# PROC010B_PMIC_Reference.net
KiCad netlist of a schematic drawn in Altium Designer
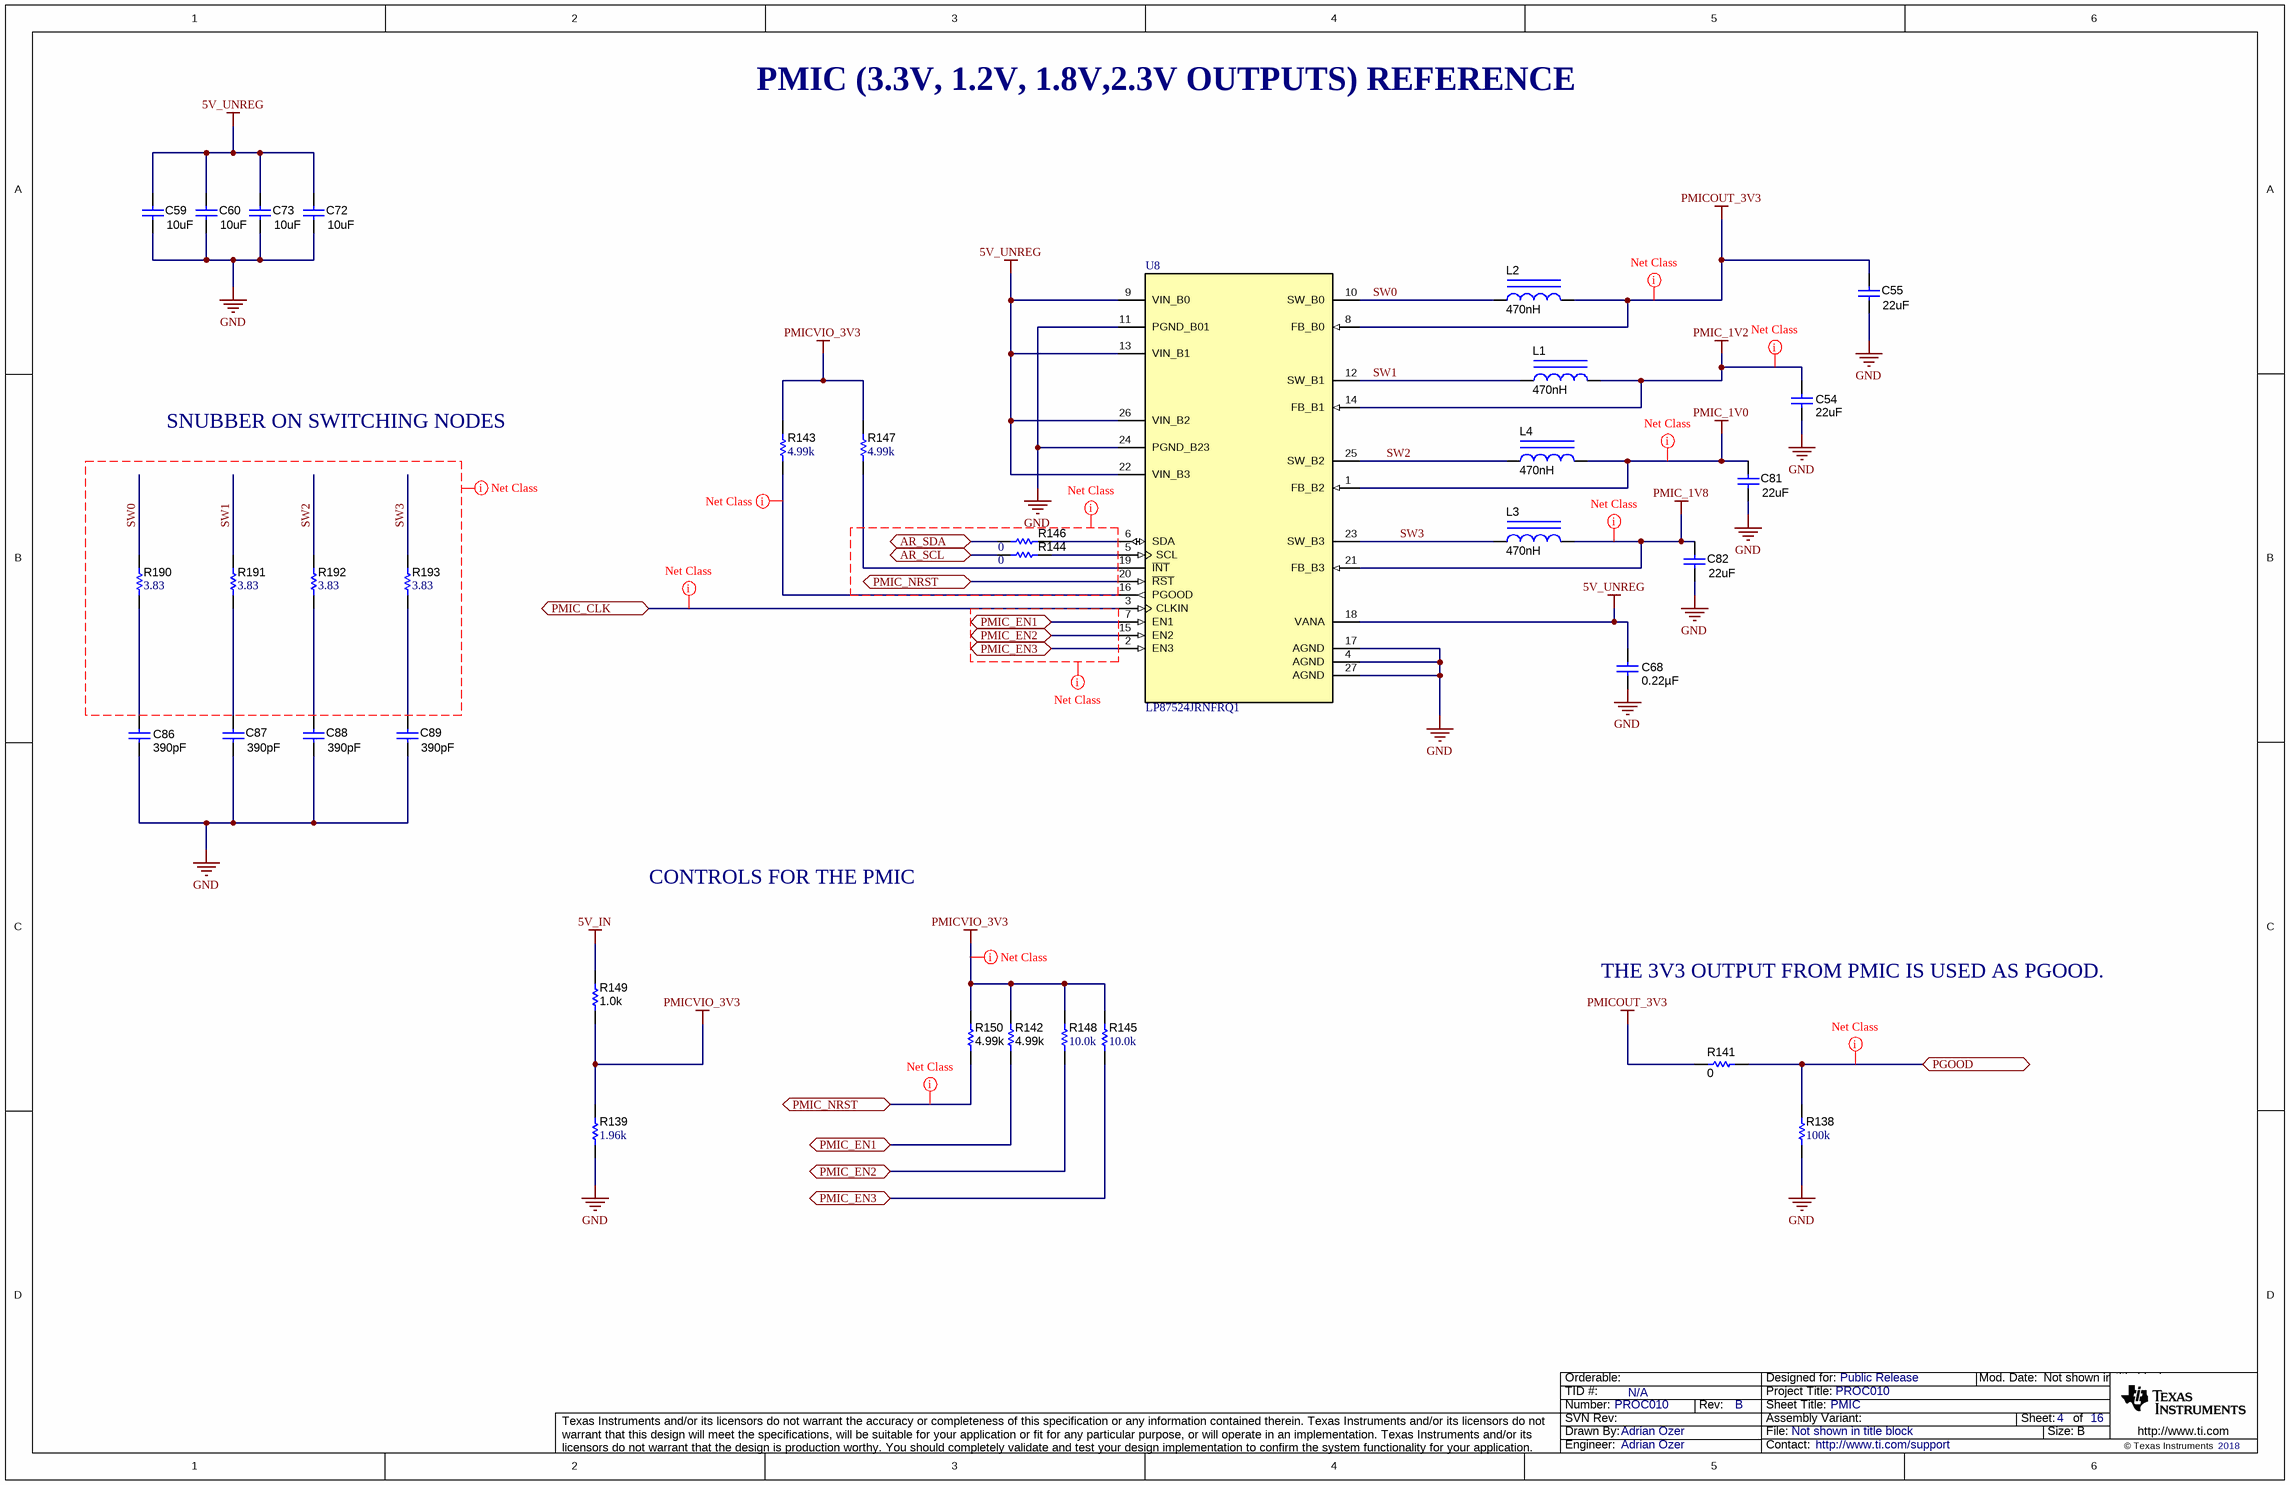
[diagram p0: PROC010B_PMIC_Reference.SchDoc]

(export (version "E")
  (design (tool "Eeschema 10.0.6"))
  (components
    (comp (ref "C54")
      (value "GCM31CR71A226KE02")
      (footprint "1206_180")
      (description "CAP, CERM, 22 uF, 10 V, +/- 10%, X7R, AEC-Q200 Grade 1, 1206")
      (fields
        (field (name "MANUFACTURER") "MuRata")
        (field (name "VALUEDISPLAYED") "22uF")
        (field (name "PUBLISHER") "Texas Instruments")
      )
      (libsource (lib "Altium Vault - TI") (part "CMP-0008811-2"))
    )
    (comp (ref "C55")
      (value "GCM31CR71A226KE02")
      (footprint "1206_180")
      (description "CAP, CERM, 22 uF, 10 V, +/- 10%, X7R, AEC-Q200 Grade 1, 1206")
      (fields
        (field (name "MANUFACTURER") "MuRata")
        (field (name "VALUEDISPLAYED") "22uF")
        (field (name "PUBLISHER") "Texas Instruments")
      )
      (libsource (lib "Altium Vault - TI") (part "Capacitor"))
    )
    (comp (ref "C59")
      (value "GCM21BR71A106KE22L")
      (footprint "0805_HV1")
      (description "CAP, CERM, 10 uF, 10 V, +/- 10%, X7R, 0805")
      (fields
        (field (name "MANUFACTURER") "MuRata")
        (field (name "VALUEDISPLAYED") "10uF")
        (field (name "PUBLISHER") "Texas Instruments")
      )
      (libsource (lib "Altium Vault - TI") (part "CMP-0008017-2"))
    )
    (comp (ref "C60")
      (value "GCM21BR71A106KE22L")
      (footprint "0805_HV1")
      (description "CAP, CERM, 10 uF, 10 V, +/- 10%, X7R, 0805")
      (fields
        (field (name "MANUFACTURER") "MuRata")
        (field (name "VALUEDISPLAYED") "10uF")
        (field (name "PUBLISHER") "Texas Instruments")
      )
      (libsource (lib "Altium Vault - TI") (part "CMP-0008017-2"))
    )
    (comp (ref "C68")
      (value "GCM155R71C224KE02D")
      (footprint "0402L")
      (description "CAP, CERM, 0.22 µF, 16 V,+/- 10%, X7R, AEC-Q200 Grade 1, 0402")
      (fields (field (name "MANUFACTURER") "MuRata") (field (name "VALUEDISPLAYED") "0.22µF"))
      (libsource (lib "Altium Vault - TI") (part "CMP-0078265-1"))
    )
    (comp (ref "C72")
      (value "GCM21BR71A106KE22L")
      (footprint "0805_HV1")
      (description "CAP, CERM, 10 uF, 10 V, +/- 10%, X7R, 0805")
      (fields
        (field (name "MANUFACTURER") "MuRata")
        (field (name "VALUEDISPLAYED") "10uF")
        (field (name "PUBLISHER") "Texas Instruments")
      )
      (libsource (lib "Altium Vault - TI") (part "CMP-0008017-2"))
    )
    (comp (ref "C73")
      (value "GCM21BR71A106KE22L")
      (footprint "0805_HV1")
      (description "CAP, CERM, 10 uF, 10 V, +/- 10%, X7R, 0805")
      (fields
        (field (name "MANUFACTURER") "MuRata")
        (field (name "VALUEDISPLAYED") "10uF")
        (field (name "PUBLISHER") "Texas Instruments")
      )
      (libsource (lib "Altium Vault - TI") (part "CMP-0008017-2"))
    )
    (comp (ref "C81")
      (value "GCM31CR71A226KE02")
      (footprint "1206_180")
      (description "CAP, CERM, 22 uF, 10 V, +/- 10%, X7R, AEC-Q200 Grade 1, 1206")
      (fields
        (field (name "MANUFACTURER") "MuRata")
        (field (name "VALUEDISPLAYED") "22uF")
        (field (name "PUBLISHER") "Texas Instruments")
      )
      (libsource (lib "Altium Vault - TI") (part "Capacitor"))
    )
    (comp (ref "C82")
      (value "GCM31CR71A226KE02")
      (footprint "1206_180")
      (description "CAP, CERM, 22 uF, 10 V, +/- 10%, X7R, AEC-Q200 Grade 1, 1206")
      (fields
        (field (name "MANUFACTURER") "MuRata")
        (field (name "VALUEDISPLAYED") "22uF")
        (field (name "PUBLISHER") "Texas Instruments")
      )
      (libsource (lib "Altium Vault - TI") (part "Capacitor"))
    )
    (comp (ref "C86")
      (value "CGA2B2NP01H391J050BA")
      (footprint "0402L")
      (description "CAP, CERM, 390 pF, 50 V,+/- 5%, C0G/NP0, AEC-Q200 Grade 0, 0402")
      (fields (field (name "MANUFACTURER") "TDK") (field (name "VALUEDISPLAYED") "390pF"))
      (libsource (lib "Altium Vault - TI") (part "Capacitor"))
    )
    (comp (ref "C87")
      (value "CGA2B2NP01H391J050BA")
      (footprint "0402L")
      (description "CAP, CERM, 390 pF, 50 V,+/- 5%, C0G/NP0, AEC-Q200 Grade 0, 0402")
      (fields (field (name "MANUFACTURER") "TDK") (field (name "VALUEDISPLAYED") "390pF"))
      (libsource (lib "Altium Vault - TI") (part "Capacitor"))
    )
    (comp (ref "C88")
      (value "CGA2B2NP01H391J050BA")
      (footprint "0402L")
      (description "CAP, CERM, 390 pF, 50 V,+/- 5%, C0G/NP0, AEC-Q200 Grade 0, 0402")
      (fields (field (name "MANUFACTURER") "TDK") (field (name "VALUEDISPLAYED") "390pF"))
      (libsource (lib "Altium Vault - TI") (part "Capacitor"))
    )
    (comp (ref "C89")
      (value "CGA2B2NP01H391J050BA")
      (footprint "0402L")
      (description "CAP, CERM, 390 pF, 50 V,+/- 5%, C0G/NP0, AEC-Q200 Grade 0, 0402")
      (fields (field (name "MANUFACTURER") "TDK") (field (name "VALUEDISPLAYED") "390pF"))
      (libsource (lib "Altium Vault - TI") (part "Capacitor"))
    )
    (comp (ref "L1")
      (value "DFE252012P-R47M=P2")
      (footprint "DFE252012P")
      (description "Inductor, Shielded, 470 nH, 4.7 A, 0.021 ohm, SMD")
      (fields
        (field (name "MANUFACTURER") "MuRata Toko")
        (field (name "VALUEDISPLAYED") "470nH")
        (field (name "PUBLISHER") "Texas Instruments")
      )
      (libsource (lib "Altium Vault - TI") (part "Inductor_Iron"))
    )
    (comp (ref "L2")
      (value "DFE252012P-R47M=P2")
      (footprint "DFE252012P")
      (description "Inductor, Shielded, 470 nH, 4.7 A, 0.021 ohm, SMD")
      (fields
        (field (name "MANUFACTURER") "MuRata Toko")
        (field (name "VALUEDISPLAYED") "470nH")
        (field (name "PUBLISHER") "Texas Instruments")
      )
      (libsource (lib "Altium Vault - TI") (part "Inductor_Iron"))
    )
    (comp (ref "L3")
      (value "DFE252012P-R47M=P2")
      (footprint "DFE252012P")
      (description "Inductor, Shielded, 470 nH, 4.7 A, 0.021 ohm, SMD")
      (fields
        (field (name "MANUFACTURER") "MuRata Toko")
        (field (name "VALUEDISPLAYED") "470nH")
        (field (name "PUBLISHER") "Texas Instruments")
      )
      (libsource (lib "Altium Vault - TI") (part "Inductor_Iron"))
    )
    (comp (ref "L4")
      (value "DFE252012P-R47M=P2")
      (footprint "DFE252012P")
      (description "Inductor, Shielded, 470 nH, 4.7 A, 0.021 ohm, SMD")
      (fields
        (field (name "MANUFACTURER") "MuRata Toko")
        (field (name "VALUEDISPLAYED") "470nH")
        (field (name "PUBLISHER") "Texas Instruments")
      )
      (libsource (lib "Altium Vault - TI") (part "Inductor_Iron"))
    )
    (comp (ref "R138")
      (value "CRCW0402100KFKED")
      (footprint "0402L")
      (description "RES, 100 k, 1%, 0.063 W, AEC-Q200 Grade 0, 0402")
      (fields (field (name "MANUFACTURER") "Vishay-Dale") (field (name "VALUEDISPLAYED") "100k"))
      (libsource (lib "Altium Vault - TI") (part "Resistor"))
    )
    (comp (ref "R139")
      (value "CRCW04021K96FKED")
      (footprint "0402L")
      (description "RES, 1.96 k, 1%, 0.063 W, AEC-Q200 Grade 0, 0402")
      (fields (field (name "MANUFACTURER") "Vishay-Dale") (field (name "VALUEDISPLAYED") "1.96k"))
      (libsource (lib "Altium Vault - TI") (part "Resistor"))
    )
    (comp (ref "R141")
      (value "ERJ-2GE0R00X")
      (footprint "0402L")
      (description "RES, 0, 5%, 0.063 W, 0402")
      (fields
        (field (name "MANUFACTURER") "Panasonic")
        (field (name "VALUEDISPLAYED") "0")
        (field (name "PUBLISHER") "Texas Instruments")
      )
      (libsource (lib "Altium Vault - TI") (part "Resistor"))
    )
    (comp (ref "R142")
      (value "ERJ-2RKF4991X")
      (footprint "0402L")
      (description "RES, 4.99 k, 1%, 0.1 W, AEC-Q200 Grade 0, 0402")
      (fields
        (field (name "MANUFACTURER") "Panasonic")
        (field (name "VALUEDISPLAYED") "4.99k")
        (field (name "PUBLISHER") "Texas Instruments")
      )
      (libsource (lib "Altium Vault - TI") (part "Resistor"))
    )
    (comp (ref "R143")
      (value "CRCW04024K99FKED")
      (footprint "0402L")
      (description "RES, 4.99 k, 1%, 0.063 W, AEC-Q200 Grade 0, 0402")
      (fields (field (name "MANUFACTURER") "Vishay-Dale") (field (name "VALUEDISPLAYED") "4.99k"))
      (libsource (lib "Altium Vault - TI") (part "Resistor"))
    )
    (comp (ref "R144")
      (value "CRCW02010000Z0ED")
      (footprint "0201_Silk")
      (description "RES, 0, 5%, 0.05 W, 0201")
      (fields (field (name "MANUFACTURER") "Vishay-Dale") (field (name "VALUEDISPLAYED") "0"))
      (libsource (lib "Altium Vault - TI") (part "Resistor"))
    )
    (comp (ref "R145")
      (value "CRCW040210K0FKED")
      (footprint "0402L")
      (description "RES, 10.0 k, 1%, 0.063 W, AEC-Q200 Grade 0, 0402")
      (fields (field (name "MANUFACTURER") "Vishay-Dale") (field (name "VALUEDISPLAYED") "10.0k"))
      (libsource (lib "Altium Vault - TI") (part "CMP-0025958-3"))
    )
    (comp (ref "R146")
      (value "CRCW02010000Z0ED")
      (footprint "0201_Silk")
      (description "RES, 0, 5%, 0.05 W, 0201")
      (fields (field (name "MANUFACTURER") "Vishay-Dale") (field (name "VALUEDISPLAYED") "0"))
      (libsource (lib "Altium Vault - TI") (part "Resistor"))
    )
    (comp (ref "R147")
      (value "CRCW04024K99FKED")
      (footprint "0402L")
      (description "RES, 4.99 k, 1%, 0.063 W, AEC-Q200 Grade 0, 0402")
      (fields (field (name "MANUFACTURER") "Vishay-Dale") (field (name "VALUEDISPLAYED") "4.99k"))
      (libsource (lib "Altium Vault - TI") (part "Resistor"))
    )
    (comp (ref "R148")
      (value "CRCW040210K0FKED")
      (footprint "0402L")
      (description "RES, 10.0 k, 1%, 0.063 W, AEC-Q200 Grade 0, 0402")
      (fields (field (name "MANUFACTURER") "Vishay-Dale") (field (name "VALUEDISPLAYED") "10.0k"))
      (libsource (lib "Altium Vault - TI") (part "Resistor"))
    )
    (comp (ref "R149")
      (value "ERJ-2GEJ102X")
      (footprint "0402L")
      (description "RES, 1.0 k, 5%, 0.1 W, AEC-Q200 Grade 0, 0402")
      (fields (field (name "MANUFACTURER") "Panasonic") (field (name "VALUEDISPLAYED") "1.0k"))
      (libsource (lib "Altium Vault - TI") (part "Resistor"))
    )
    (comp (ref "R150")
      (value "ERJ-2RKF4991X")
      (footprint "0402L")
      (description "RES, 4.99 k, 1%, 0.1 W, AEC-Q200 Grade 0, 0402")
      (fields
        (field (name "MANUFACTURER") "Panasonic")
        (field (name "VALUEDISPLAYED") "4.99k")
        (field (name "PUBLISHER") "Texas Instruments")
      )
      (libsource (lib "Altium Vault - TI") (part "Resistor"))
    )
    (comp (ref "R190")
      (value "CRCW04023R83FKED")
      (footprint "0402L")
      (description "RES, 3.83, 1%, 0.063 W, AEC-Q200 Grade 0, 0402")
      (fields (field (name "MANUFACTURER") "Vishay-Dale") (field (name "VALUEDISPLAYED") "3.83"))
      (libsource (lib "Altium Vault - TI") (part "Resistor"))
    )
    (comp (ref "R191")
      (value "CRCW04023R83FKED")
      (footprint "0402L")
      (description "RES, 3.83, 1%, 0.063 W, AEC-Q200 Grade 0, 0402")
      (fields (field (name "MANUFACTURER") "Vishay-Dale") (field (name "VALUEDISPLAYED") "3.83"))
      (libsource (lib "Altium Vault - TI") (part "Resistor"))
    )
    (comp (ref "R192")
      (value "CRCW04023R83FKED")
      (footprint "0402L")
      (description "RES, 3.83, 1%, 0.063 W, AEC-Q200 Grade 0, 0402")
      (fields (field (name "MANUFACTURER") "Vishay-Dale") (field (name "VALUEDISPLAYED") "3.83"))
      (libsource (lib "Altium Vault - TI") (part "Resistor"))
    )
    (comp (ref "R193")
      (value "CRCW04023R83FKED")
      (footprint "0402L")
      (description "RES, 3.83, 1%, 0.063 W, AEC-Q200 Grade 0, 0402")
      (fields (field (name "MANUFACTURER") "Vishay-Dale") (field (name "VALUEDISPLAYED") "3.83"))
      (libsource (lib "Altium Vault - TI") (part "Resistor"))
    )
    (comp (ref "U8")
      (value "LP87524JRNFRQ1")
      (footprint "RNF0026C")
      (description "4-A + 2.5-A + Two 1.5-A Buck Converters With Integrated Switches, RNF0026C (VQFN-HR-26)")
      (fields
        (field (name "ALTERNATE PARTNUMBER") "LP87524JRNFTQ1")
        (field (name "MANUFACTURER") "Texas Instruments")
        (field (name "PARTNUMBER") "LP87524JRNFRQ1")
      )
      (libsource (lib "Altium Vault - TI") (part "CMP-0079120-1"))
    )
  )
  (nets
    (net (code "1") (name "/AR_SCL") (class "Default")
      (node (ref "R144") (pin "1") (pinfunction "1_1") (pintype "passive"))
    )
    (net (code "2") (name "/AR_SDA") (class "Default")
      (node (ref "R146") (pin "2") (pinfunction "2_2") (pintype "passive"))
    )
    (net (code "3") (name "/PGOOD") (class "Default")
      (node (ref "R138") (pin "2") (pinfunction "2_2") (pintype "passive"))
      (node (ref "R141") (pin "2") (pinfunction "2_2") (pintype "passive"))
    )
    (net (code "4") (name "/PMIC_CLK") (class "Default")
      (node (ref "U8") (pin "3") (pinfunction "CLKIN_3") (pintype "input"))
    )
    (net (code "5") (name "/PMIC_EN1") (class "Default")
      (node (ref "R142") (pin "1") (pinfunction "1_1") (pintype "passive"))
      (node (ref "U8") (pin "7") (pinfunction "EN1_7") (pintype "input"))
    )
    (net (code "6") (name "/PMIC_EN2") (class "Default")
      (node (ref "R148") (pin "1") (pinfunction "1_1") (pintype "passive"))
      (node (ref "U8") (pin "15") (pinfunction "EN2_15") (pintype "input"))
    )
    (net (code "7") (name "/PMIC_EN3") (class "Default")
      (node (ref "R145") (pin "1") (pinfunction "1_1") (pintype "passive"))
      (node (ref "U8") (pin "2") (pinfunction "EN3_2") (pintype "input"))
    )
    (net (code "8") (name "/PMIC_NRST") (class "Default")
      (node (ref "R150") (pin "2") (pinfunction "2_2") (pintype "passive"))
      (node (ref "U8") (pin "20") (pinfunction "RST_20") (pintype "input"))
    )
    (net (code "9") (name "/SW0") (class "Default")
      (node (ref "L2") (pin "1") (pinfunction "1_1") (pintype "passive"))
      (node (ref "R190") (pin "2") (pinfunction "2_2") (pintype "passive"))
      (node (ref "U8") (pin "10") (pinfunction "SW_B0_10") (pintype "power_in"))
    )
    (net (code "10") (name "/SW1") (class "Default")
      (node (ref "L1") (pin "1") (pinfunction "1_1") (pintype "passive"))
      (node (ref "R191") (pin "2") (pinfunction "2_2") (pintype "passive"))
      (node (ref "U8") (pin "12") (pinfunction "SW_B1_12") (pintype "power_in"))
    )
    (net (code "11") (name "/SW2") (class "Default")
      (node (ref "L4") (pin "1") (pinfunction "1_1") (pintype "passive"))
      (node (ref "R192") (pin "2") (pinfunction "2_2") (pintype "passive"))
      (node (ref "U8") (pin "25") (pinfunction "SW_B2_25") (pintype "power_in"))
    )
    (net (code "12") (name "/SW3") (class "Default")
      (node (ref "L3") (pin "1") (pinfunction "1_1") (pintype "passive"))
      (node (ref "R193") (pin "2") (pinfunction "2_2") (pintype "passive"))
      (node (ref "U8") (pin "23") (pinfunction "SW_B3_23") (pintype "power_in"))
    )
    (net (code "13") (name "5V_IN") (class "Default")
      (node (ref "R149") (pin "2") (pinfunction "2_2") (pintype "passive"))
    )
    (net (code "14") (name "5V_UNREG") (class "Default")
      (node (ref "C59") (pin "2") (pinfunction "2_2") (pintype "passive"))
      (node (ref "C60") (pin "2") (pinfunction "2_2") (pintype "passive"))
      (node (ref "C68") (pin "2") (pinfunction "2_2") (pintype "passive"))
      (node (ref "C72") (pin "2") (pinfunction "2_2") (pintype "passive"))
      (node (ref "C73") (pin "2") (pinfunction "2_2") (pintype "passive"))
      (node (ref "U8") (pin "13") (pinfunction "VIN_B1_13") (pintype "power_in"))
      (node (ref "U8") (pin "18") (pinfunction "VANA_18") (pintype "power_in"))
      (node (ref "U8") (pin "22") (pinfunction "VIN_B3_22") (pintype "power_in"))
      (node (ref "U8") (pin "26") (pinfunction "VIN_B2_26") (pintype "power_in"))
      (node (ref "U8") (pin "9") (pinfunction "VIN_B0_9") (pintype "power_in"))
    )
    (net (code "15") (name "GND") (class "Default")
      (node (ref "C54") (pin "1") (pinfunction "1_1") (pintype "passive"))
      (node (ref "C55") (pin "1") (pinfunction "1_1") (pintype "passive"))
      (node (ref "C59") (pin "1") (pinfunction "1_1") (pintype "passive"))
      (node (ref "C60") (pin "1") (pinfunction "1_1") (pintype "passive"))
      (node (ref "C68") (pin "1") (pinfunction "1_1") (pintype "passive"))
      (node (ref "C72") (pin "1") (pinfunction "1_1") (pintype "passive"))
      (node (ref "C73") (pin "1") (pinfunction "1_1") (pintype "passive"))
      (node (ref "C81") (pin "1") (pinfunction "1_1") (pintype "passive"))
      (node (ref "C82") (pin "1") (pinfunction "1_1") (pintype "passive"))
      (node (ref "C86") (pin "1") (pinfunction "1_1") (pintype "passive"))
      (node (ref "C87") (pin "1") (pinfunction "1_1") (pintype "passive"))
      (node (ref "C88") (pin "1") (pinfunction "1_1") (pintype "passive"))
      (node (ref "C89") (pin "1") (pinfunction "1_1") (pintype "passive"))
      (node (ref "R138") (pin "1") (pinfunction "1_1") (pintype "passive"))
      (node (ref "R139") (pin "1") (pinfunction "1_1") (pintype "passive"))
      (node (ref "U8") (pin "11") (pinfunction "PGND_B01_11") (pintype "power_in"))
      (node (ref "U8") (pin "17") (pinfunction "AGND_17") (pintype "power_in"))
      (node (ref "U8") (pin "24") (pinfunction "PGND_B23_24") (pintype "power_in"))
      (node (ref "U8") (pin "27") (pinfunction "AGND_27") (pintype "power_in"))
      (node (ref "U8") (pin "4") (pinfunction "AGND_4") (pintype "power_in"))
    )
    (net (code "16") (name "Net-(C86-Pad2)") (class "Default")
      (node (ref "C86") (pin "2") (pinfunction "2_2") (pintype "passive"))
      (node (ref "R190") (pin "1") (pinfunction "1_1") (pintype "passive"))
    )
    (net (code "17") (name "Net-(C87-Pad2)") (class "Default")
      (node (ref "C87") (pin "2") (pinfunction "2_2") (pintype "passive"))
      (node (ref "R191") (pin "1") (pinfunction "1_1") (pintype "passive"))
    )
    (net (code "18") (name "Net-(C88-Pad2)") (class "Default")
      (node (ref "C88") (pin "2") (pinfunction "2_2") (pintype "passive"))
      (node (ref "R192") (pin "1") (pinfunction "1_1") (pintype "passive"))
    )
    (net (code "19") (name "Net-(C89-Pad2)") (class "Default")
      (node (ref "C89") (pin "2") (pinfunction "2_2") (pintype "passive"))
      (node (ref "R193") (pin "1") (pinfunction "1_1") (pintype "passive"))
    )
    (net (code "20") (name "Net-(U8-INT)") (class "Default")
      (node (ref "R147") (pin "1") (pinfunction "1_1") (pintype "passive"))
      (node (ref "U8") (pin "19") (pinfunction "INT_19") (pintype "open_collector"))
    )
    (net (code "21") (name "Net-(U8-PGOOD)") (class "Default")
      (node (ref "R143") (pin "1") (pinfunction "1_1") (pintype "passive"))
      (node (ref "U8") (pin "16") (pinfunction "PGOOD_16") (pintype "output"))
    )
    (net (code "22") (name "Net-(U8-SCL)") (class "Default")
      (node (ref "R144") (pin "2") (pinfunction "2_2") (pintype "passive"))
      (node (ref "U8") (pin "5") (pinfunction "SCL_5") (pintype "input"))
    )
    (net (code "23") (name "Net-(U8-SDA)") (class "Default")
      (node (ref "R146") (pin "1") (pinfunction "1_1") (pintype "passive"))
      (node (ref "U8") (pin "6") (pinfunction "SDA_6") (pintype "bidirectional"))
    )
    (net (code "24") (name "PMICOUT_3V3") (class "Default")
      (node (ref "C55") (pin "2") (pinfunction "2_2") (pintype "passive"))
      (node (ref "L2") (pin "2") (pinfunction "2_2") (pintype "passive"))
      (node (ref "R141") (pin "1") (pinfunction "1_1") (pintype "passive"))
      (node (ref "U8") (pin "8") (pinfunction "FB_B0_8") (pintype "input"))
    )
    (net (code "25") (name "PMICVIO_3V3") (class "Default")
      (node (ref "R139") (pin "2") (pinfunction "2_2") (pintype "passive"))
      (node (ref "R142") (pin "2") (pinfunction "2_2") (pintype "passive"))
      (node (ref "R143") (pin "2") (pinfunction "2_2") (pintype "passive"))
      (node (ref "R145") (pin "2") (pinfunction "2_2") (pintype "passive"))
      (node (ref "R147") (pin "2") (pinfunction "2_2") (pintype "passive"))
      (node (ref "R148") (pin "2") (pinfunction "2_2") (pintype "passive"))
      (node (ref "R149") (pin "1") (pinfunction "1_1") (pintype "passive"))
      (node (ref "R150") (pin "1") (pinfunction "1_1") (pintype "passive"))
    )
    (net (code "26") (name "PMIC_1V0") (class "Default")
      (node (ref "C81") (pin "2") (pinfunction "2_2") (pintype "passive"))
      (node (ref "L4") (pin "2") (pinfunction "2_2") (pintype "passive"))
      (node (ref "U8") (pin "1") (pinfunction "FB_B2_1") (pintype "input"))
    )
    (net (code "27") (name "PMIC_1V2") (class "Default")
      (node (ref "C54") (pin "2") (pinfunction "2_2") (pintype "passive"))
      (node (ref "L1") (pin "2") (pinfunction "2_2") (pintype "passive"))
      (node (ref "U8") (pin "14") (pinfunction "FB_B1_14") (pintype "input"))
    )
    (net (code "28") (name "PMIC_1V8") (class "Default")
      (node (ref "C82") (pin "2") (pinfunction "2_2") (pintype "passive"))
      (node (ref "L3") (pin "2") (pinfunction "2_2") (pintype "passive"))
      (node (ref "U8") (pin "21") (pinfunction "FB_B3_21") (pintype "input"))
    )
  )
)
